# MAX6605.net
KiCad netlist of a schematic drawn in Altium Designer
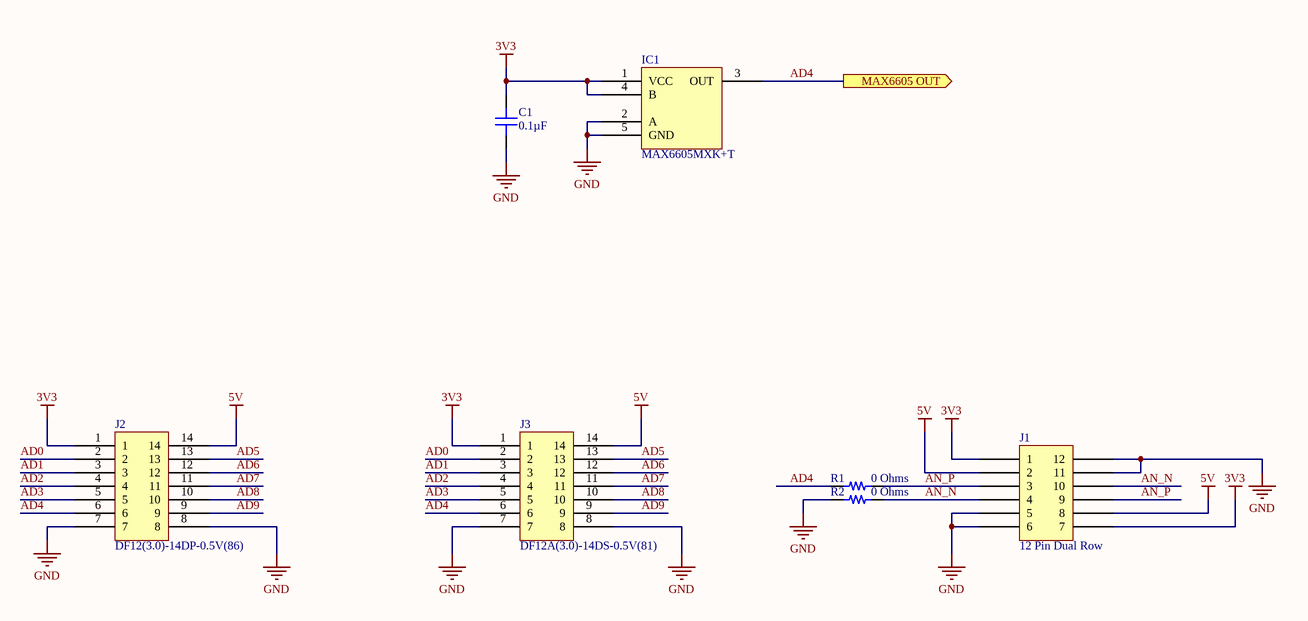
[diagram p0: MAX6605.SchDoc]

(export (version "E")
  (design (tool "Eeschema 10.0.6"))
  (components
    (comp (ref "C1")
      (value "0.1µF")
      (footprint "CAP 0603_1608")
      (description "CAP CER 0.1UF 16V Y5V 0603")
      (fields (field (name "PART NUMBER") "CC0603ZRY5V7BB104") (field (name "MANUFACTURER") "Yageo"))
      (libsource (lib "altiumlibrary.com") (part "Capacitor"))
    )
    (comp (ref "IC1")
      (value "MAX6605MXK+T")
      (footprint "MAXIM SC-70-5 X5-1")
      (description "SENSOR ANALOG -55C-125C SC70-5")
      (fields (field (name "MANUFACTURER") "Maxim Integrated"))
      (libsource (lib "altiumlibrary.com") (part "Maxim MAX6605"))
    )
    (comp (ref "J1")
      (value "12 Pin Dual Row")
      (footprint "TE 5650118-3 Card Edge")
      (libsource (lib "CelestialUseful") (part "12 Pin Dual Row"))
    )
    (comp (ref "J2")
      (value "DF12(3.0)-14DP-0.5V(86)")
      (footprint "HIROSE DF12 3.0-14DP-0.5V 86")
      (description "CONN HDR 14POS SMD GOLD")
      (fields (field (name "MANUFACTURER") "Hirose Electric Co Ltd"))
      (libsource (lib "altiumlibrary.com") (part "14 Pin Dual Row"))
    )
    (comp (ref "J3")
      (value "DF12A(3.0)-14DS-0.5V(81)")
      (footprint "HIROSE DF12A 3.0-14DS-0.5V 81")
      (description "CONN RCPT 14POS SMD GOLD")
      (fields (field (name "MANUFACTURER") "Hirose Electric Co Ltd"))
      (libsource (lib "altiumlibrary.com") (part "14 Pin Dual Row"))
    )
    (comp (ref "R1")
      (value "0 Ohms")
      (footprint "RES 0603_1608")
      (description "RES SMD 0 OHM JUMPER 1/10W 0603")
      (fields
        (field (name "PART NUMBER") "ERJ-3GEY0R00V")
        (field (name "MANUFACTURER") "Panasonic Electronic Components")
      )
      (libsource (lib "altiumlibrary.com") (part "Resistor"))
    )
    (comp (ref "R2")
      (value "0 Ohms")
      (footprint "RES 0603_1608")
      (description "RES SMD 0 OHM JUMPER 1/10W 0603")
      (fields
        (field (name "PART NUMBER") "ERJ-3GEY0R00V")
        (field (name "MANUFACTURER") "Panasonic Electronic Components")
      )
      (libsource (lib "altiumlibrary.com") (part "Resistor"))
    )
  )
  (nets
    (net (code "1") (name "/AD0") (class "Default")
      (node (ref "J2") (pin "2") (pinfunction "2_2") (pintype "passive"))
      (node (ref "J3") (pin "2") (pinfunction "2_2") (pintype "passive"))
    )
    (net (code "2") (name "/AD1") (class "Default")
      (node (ref "J2") (pin "3") (pinfunction "3_3") (pintype "passive"))
      (node (ref "J3") (pin "3") (pinfunction "3_3") (pintype "passive"))
    )
    (net (code "3") (name "/AD2") (class "Default")
      (node (ref "J2") (pin "4") (pinfunction "4_4") (pintype "passive"))
      (node (ref "J3") (pin "4") (pinfunction "4_4") (pintype "passive"))
    )
    (net (code "4") (name "/AD3") (class "Default")
      (node (ref "J2") (pin "5") (pinfunction "5_5") (pintype "passive"))
      (node (ref "J3") (pin "5") (pinfunction "5_5") (pintype "passive"))
    )
    (net (code "5") (name "/AD4") (class "Default")
      (node (ref "IC1") (pin "3") (pinfunction "OUT_3") (pintype "passive"))
      (node (ref "J2") (pin "6") (pinfunction "6_6") (pintype "passive"))
      (node (ref "J3") (pin "6") (pinfunction "6_6") (pintype "passive"))
      (node (ref "R1") (pin "1") (pinfunction "1_1") (pintype "passive"))
    )
    (net (code "6") (name "/AD5") (class "Default")
      (node (ref "J2") (pin "13") (pinfunction "13_13") (pintype "passive"))
      (node (ref "J3") (pin "13") (pinfunction "13_13") (pintype "passive"))
    )
    (net (code "7") (name "/AD6") (class "Default")
      (node (ref "J2") (pin "12") (pinfunction "12_12") (pintype "passive"))
      (node (ref "J3") (pin "12") (pinfunction "12_12") (pintype "passive"))
    )
    (net (code "8") (name "/AD7") (class "Default")
      (node (ref "J2") (pin "11") (pinfunction "11_11") (pintype "passive"))
      (node (ref "J3") (pin "11") (pinfunction "11_11") (pintype "passive"))
    )
    (net (code "9") (name "/AD8") (class "Default")
      (node (ref "J2") (pin "10") (pinfunction "10_10") (pintype "passive"))
      (node (ref "J3") (pin "10") (pinfunction "10_10") (pintype "passive"))
    )
    (net (code "10") (name "/AD9") (class "Default")
      (node (ref "J2") (pin "9") (pinfunction "9_9") (pintype "passive"))
      (node (ref "J3") (pin "9") (pinfunction "9_9") (pintype "passive"))
    )
    (net (code "11") (name "/AN_N") (class "Default")
      (node (ref "J1") (pin "10") (pinfunction "10_10") (pintype "passive"))
      (node (ref "J1") (pin "4") (pinfunction "4_4") (pintype "passive"))
      (node (ref "R2") (pin "2") (pinfunction "2_2") (pintype "passive"))
    )
    (net (code "12") (name "/AN_P") (class "Default")
      (node (ref "J1") (pin "3") (pinfunction "3_3") (pintype "passive"))
      (node (ref "J1") (pin "9") (pinfunction "9_9") (pintype "passive"))
      (node (ref "R1") (pin "2") (pinfunction "2_2") (pintype "passive"))
    )
    (net (code "13") (name "3V3") (class "Default")
      (node (ref "C1") (pin "1") (pinfunction "1_1") (pintype "passive"))
      (node (ref "IC1") (pin "1") (pinfunction "VCC_1") (pintype "passive"))
      (node (ref "IC1") (pin "4") (pinfunction "B_4") (pintype "passive"))
      (node (ref "J1") (pin "1") (pinfunction "1_1") (pintype "passive"))
      (node (ref "J1") (pin "7") (pinfunction "7_7") (pintype "passive"))
      (node (ref "J2") (pin "1") (pinfunction "1_1") (pintype "passive"))
      (node (ref "J3") (pin "1") (pinfunction "1_1") (pintype "passive"))
    )
    (net (code "14") (name "5V") (class "Default")
      (node (ref "J1") (pin "2") (pinfunction "2_2") (pintype "passive"))
      (node (ref "J1") (pin "8") (pinfunction "8_8") (pintype "passive"))
      (node (ref "J2") (pin "14") (pinfunction "14_14") (pintype "passive"))
      (node (ref "J3") (pin "14") (pinfunction "14_14") (pintype "passive"))
    )
    (net (code "15") (name "GND") (class "Default")
      (node (ref "C1") (pin "2") (pinfunction "2_2") (pintype "passive"))
      (node (ref "IC1") (pin "2") (pinfunction "A_2") (pintype "passive"))
      (node (ref "IC1") (pin "5") (pinfunction "GND_5") (pintype "passive"))
      (node (ref "J1") (pin "11") (pinfunction "11_11") (pintype "passive"))
      (node (ref "J1") (pin "12") (pinfunction "12_12") (pintype "passive"))
      (node (ref "J1") (pin "5") (pinfunction "5_5") (pintype "passive"))
      (node (ref "J1") (pin "6") (pinfunction "6_6") (pintype "passive"))
      (node (ref "J2") (pin "7") (pinfunction "7_7") (pintype "passive"))
      (node (ref "J2") (pin "8") (pinfunction "8_8") (pintype "passive"))
      (node (ref "J3") (pin "7") (pinfunction "7_7") (pintype "passive"))
      (node (ref "J3") (pin "8") (pinfunction "8_8") (pintype "passive"))
      (node (ref "R2") (pin "1") (pinfunction "1_1") (pintype "passive"))
    )
  )
)
